# ArduiPi_V1_1.net
KiCad netlist of a schematic drawn in EAGLE
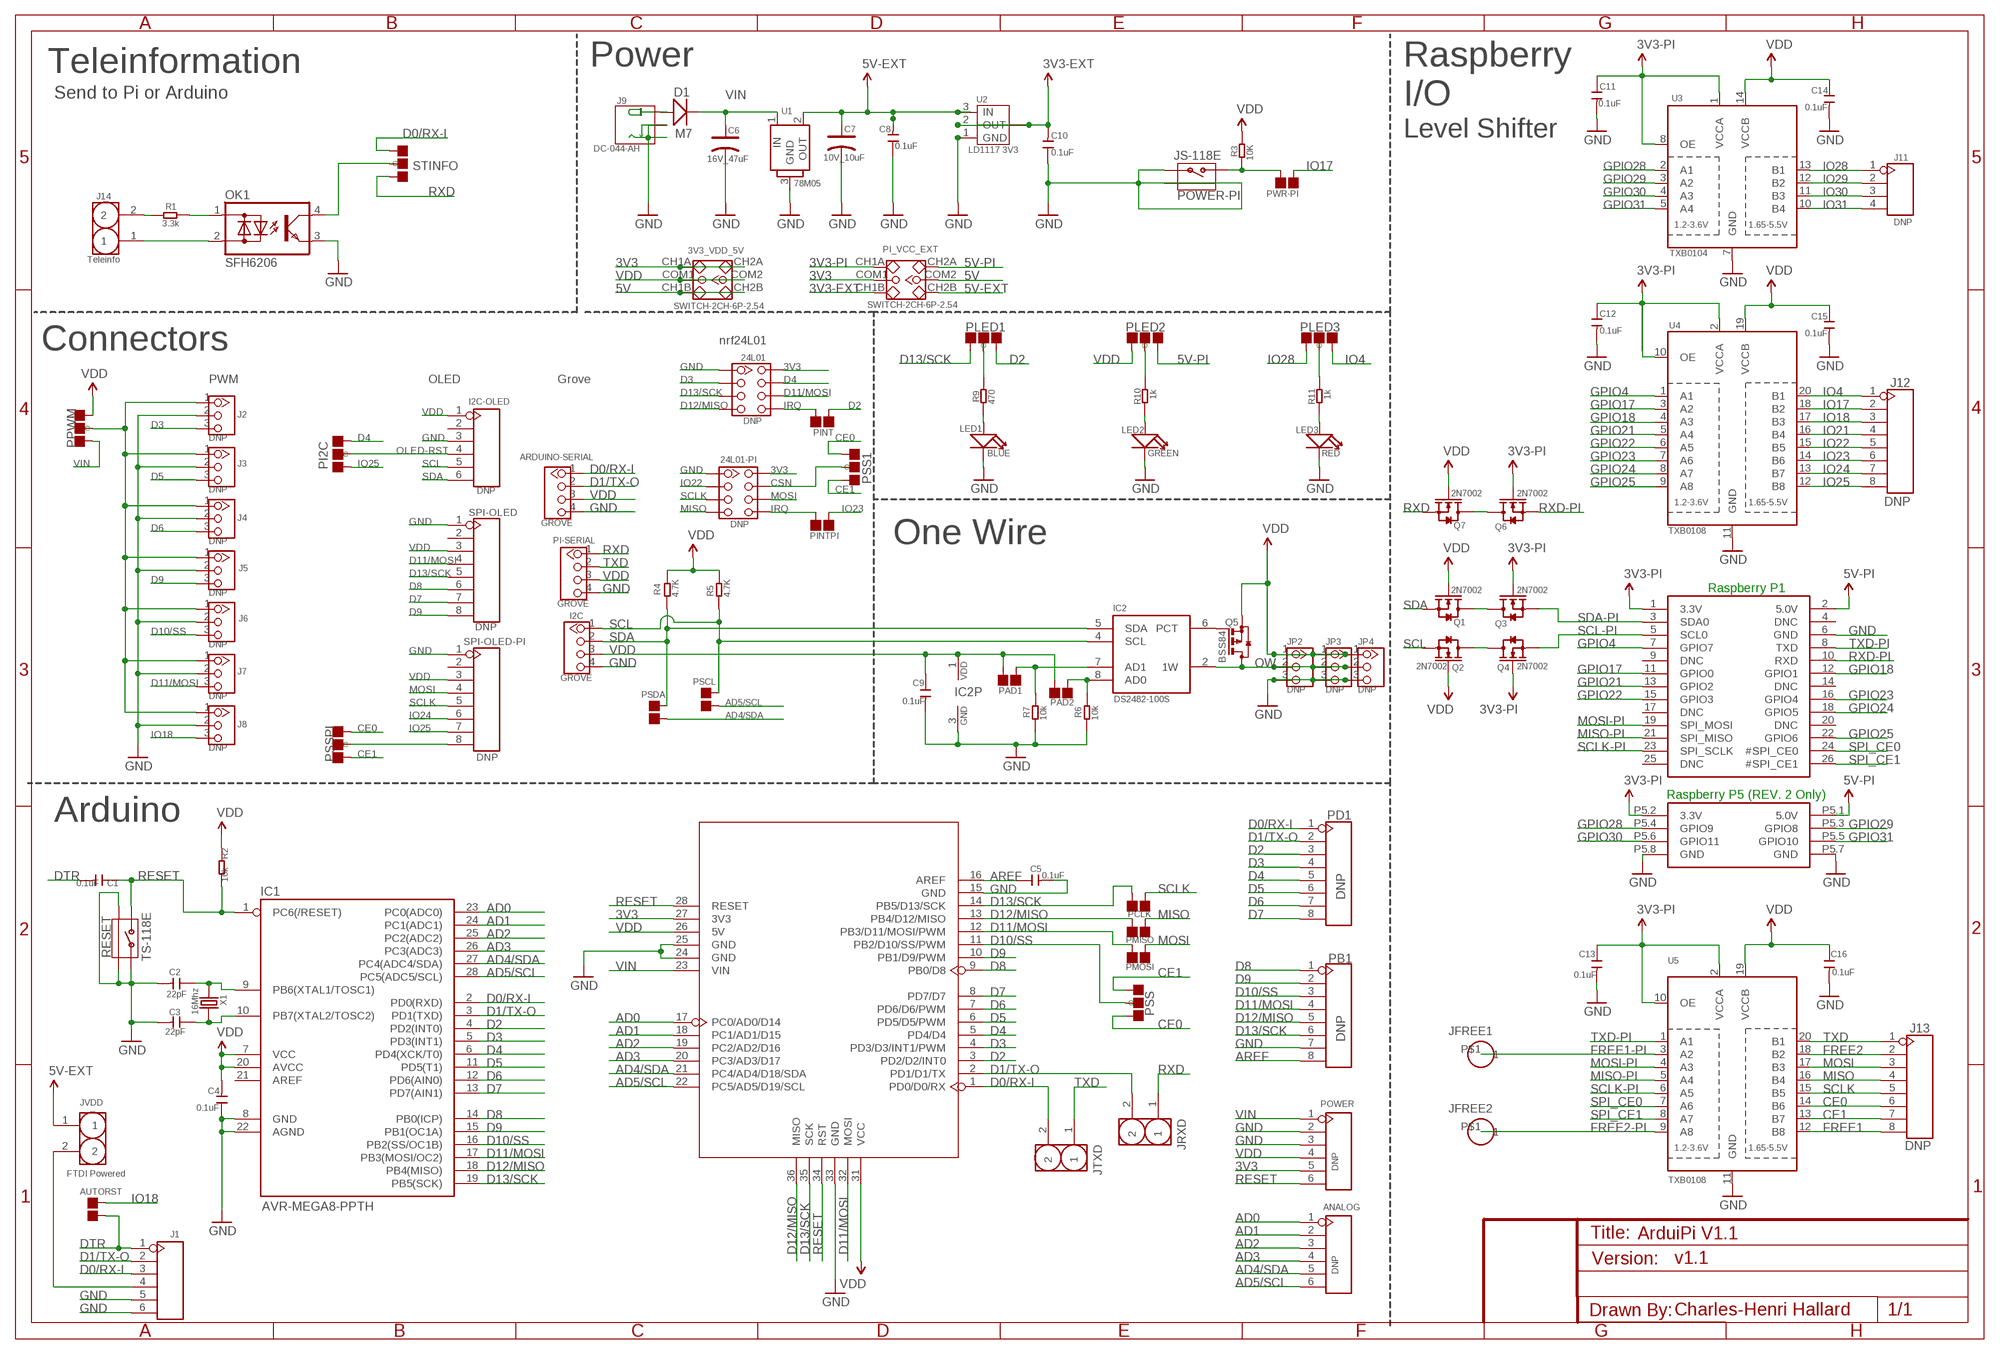
[diagram p0: schematic, sheet 1]

(export (version "E")
  (design (tool "Eeschema 10.0.6"))
  (components
    (comp (ref "3V3_VDD_5V")
      (value "SWITCH-2CH-6P-2.54")
      (footprint "eagle-import:6P-2CH-2.54-7.6X3.0")
      (libsource (lib "eagle-import") (part "SWITCH-2CH-6P"))
    )
    (comp (ref "24L01")
      (value "DNP")
      (footprint "eagle-import:2X4P-2.54")
      (libsource (lib "eagle-import") (part "HEADER-2X4P-2.54"))
    )
    (comp (ref "24L01-PI")
      (value "DNP")
      (footprint "eagle-import:2X4P-2.54")
      (libsource (lib "eagle-import") (part "HEADER-2X4P-2.54"))
    )
    (comp (ref "ANALOG")
      (value "DNP")
      (footprint "eagle-import:6P-2.54-65_35MIL")
      (libsource (lib "eagle-import") (part "HEADER-6P-65/35MIL"))
    )
    (comp (ref "ARDUINO-SERIAL")
      (value "GROVE")
      (footprint "eagle-import:4P-LEADED-2.0")
      (libsource (lib "eagle-import") (part "TWIG-2.0-LEADED"))
    )
    (comp (ref "AUTORST")
      (value "PSDA")
      (footprint "eagle-import:2P-SMD-1.78X1.27")
      (fields (field (name "PARTNO") "DNP"))
      (libsource (lib "eagle-import") (part "PAD-JUMPER-2P"))
    )
    (comp (ref "C1")
      (value "0.1uF")
      (footprint "eagle-import:C0603")
      (libsource (lib "eagle-import") (part "C-0603"))
    )
    (comp (ref "C2")
      (value "22pF")
      (footprint "eagle-import:C0603")
      (libsource (lib "eagle-import") (part "C-0603"))
    )
    (comp (ref "C3")
      (value "22pF")
      (footprint "eagle-import:C0603")
      (libsource (lib "eagle-import") (part "C-0603"))
    )
    (comp (ref "C4")
      (value "0.1uF")
      (footprint "eagle-import:C0603")
      (libsource (lib "eagle-import") (part "C-0603"))
    )
    (comp (ref "C5")
      (value "0.1uF")
      (footprint "eagle-import:C0603")
      (libsource (lib "eagle-import") (part "C-0603"))
    )
    (comp (ref "C6")
      (value "16V_47uF")
      (footprint "eagle-import:AVX-C")
      (libsource (lib "eagle-import") (part "CAP-AVX-C"))
    )
    (comp (ref "C7")
      (value "10V_10uF")
      (footprint "eagle-import:AVX-A")
      (libsource (lib "eagle-import") (part "CAP-AVX-A"))
    )
    (comp (ref "C8")
      (value "0.1uF")
      (footprint "eagle-import:C0603")
      (libsource (lib "eagle-import") (part "C-0603"))
    )
    (comp (ref "C9")
      (value "0.1uF")
      (footprint "eagle-import:C0603")
      (libsource (lib "eagle-import") (part "C-0603"))
    )
    (comp (ref "C10")
      (value "0.1uF")
      (footprint "eagle-import:C0603")
      (libsource (lib "eagle-import") (part "C-0603"))
    )
    (comp (ref "C11")
      (value "0.1uF")
      (footprint "eagle-import:C0603")
      (libsource (lib "eagle-import") (part "C-0603"))
    )
    (comp (ref "C12")
      (value "0.1uF")
      (footprint "eagle-import:C0603")
      (libsource (lib "eagle-import") (part "C-0603"))
    )
    (comp (ref "C13")
      (value "0.1uF")
      (footprint "eagle-import:C0603")
      (libsource (lib "eagle-import") (part "C-0603"))
    )
    (comp (ref "C14")
      (value "0.1uF")
      (footprint "eagle-import:C0603")
      (libsource (lib "eagle-import") (part "C-0603"))
    )
    (comp (ref "C15")
      (value "0.1uF")
      (footprint "eagle-import:C0603")
      (libsource (lib "eagle-import") (part "C-0603"))
    )
    (comp (ref "C16")
      (value "0.1uF")
      (footprint "eagle-import:C0603")
      (libsource (lib "eagle-import") (part "C-0603"))
    )
    (comp (ref "D1")
      (value "M7")
      (footprint "eagle-import:D2010")
      (libsource (lib "eagle-import") (part "D'SMA'"))
    )
    (comp (ref "I2C")
      (value "GROVE")
      (footprint "eagle-import:4P-LEADED-2.0")
      (libsource (lib "eagle-import") (part "TWIG-2.0-LEADED"))
    )
    (comp (ref "I2C-OLED")
      (value "DNP")
      (footprint "eagle-import:6P-2.54-65_35MIL")
      (libsource (lib "eagle-import") (part "HEADER-6P-65/35MIL"))
    )
    (comp (ref "IC1")
      (value "AVR-MEGA8-PPTH")
      (footprint "eagle-import:DIL28-3")
      (libsource (lib "eagle-import") (part "AVR-MEGA8-PPTH"))
    )
    (comp (ref "IC2")
      (value "DS2482-100S")
      (footprint "eagle-import:SO08")
      (libsource (lib "eagle-import") (part "DS2482-100S"))
    )
    (comp (ref "J1")
      (value "HEADER-6P-65/35MIL")
      (footprint "eagle-import:6P-2.54-65_35MIL")
      (libsource (lib "eagle-import") (part "HEADER-6P-65/35MIL"))
    )
    (comp (ref "J2")
      (value "DNP")
      (footprint "eagle-import:3P-2.54")
      (libsource (lib "eagle-import") (part "HEADER-3P-2.54"))
    )
    (comp (ref "J3")
      (value "DNP")
      (footprint "eagle-import:3P-2.54")
      (libsource (lib "eagle-import") (part "HEADER-3P-2.54"))
    )
    (comp (ref "J4")
      (value "DNP")
      (footprint "eagle-import:3P-2.54")
      (libsource (lib "eagle-import") (part "HEADER-3P-2.54"))
    )
    (comp (ref "J5")
      (value "DNP")
      (footprint "eagle-import:3P-2.54")
      (libsource (lib "eagle-import") (part "HEADER-3P-2.54"))
    )
    (comp (ref "J6")
      (value "DNP")
      (footprint "eagle-import:3P-2.54")
      (libsource (lib "eagle-import") (part "HEADER-3P-2.54"))
    )
    (comp (ref "J7")
      (value "DNP")
      (footprint "eagle-import:3P-2.54")
      (libsource (lib "eagle-import") (part "HEADER-3P-2.54"))
    )
    (comp (ref "J8")
      (value "DNP")
      (footprint "eagle-import:3P-2.54")
      (libsource (lib "eagle-import") (part "HEADER-3P-2.54"))
    )
    (comp (ref "J9")
      (value "DC-044-AH")
      (footprint "eagle-import:DC-044")
      (libsource (lib "eagle-import") (part "JACK-DC-044"))
    )
    (comp (ref "J11")
      (value "DNP")
      (footprint "eagle-import:4P-65_35MIL")
      (libsource (lib "eagle-import") (part "HEADER-4P-65/35MIL"))
    )
    (comp (ref "J12")
      (value "DNP")
      (footprint "eagle-import:8P-2.54-65_35MIL")
      (libsource (lib "eagle-import") (part "HEADER-8P-65/35MIL"))
    )
    (comp (ref "J13")
      (value "DNP")
      (footprint "eagle-import:8P-2.54-65_35MIL")
      (libsource (lib "eagle-import") (part "HEADER-8P-65/35MIL"))
    )
    (comp (ref "J14")
      (value "Teleinfo")
      (footprint "eagle-import:2P-2.54")
      (libsource (lib "eagle-import") (part "HEADER-2P-2.54"))
    )
    (comp (ref "JFREE1")
      (value "HEADER-1P-32")
      (footprint "eagle-import:1P-60_32MIL")
      (libsource (lib "eagle-import") (part "HEADER-1P-32"))
    )
    (comp (ref "JFREE2")
      (value "HEADER-1P-32")
      (footprint "eagle-import:1P-60_32MIL")
      (libsource (lib "eagle-import") (part "HEADER-1P-32"))
    )
    (comp (ref "JP2")
      (value "DNP")
      (footprint "eagle-import:3P-2.54")
      (libsource (lib "eagle-import") (part "HEADER-3P-2.54"))
    )
    (comp (ref "JP3")
      (value "DNP")
      (footprint "eagle-import:3P-2.54")
      (libsource (lib "eagle-import") (part "HEADER-3P-2.54"))
    )
    (comp (ref "JP4")
      (value "DNP")
      (footprint "eagle-import:3P-2.54")
      (libsource (lib "eagle-import") (part "HEADER-3P-2.54"))
    )
    (comp (ref "JRXD")
      (value "J2")
      (footprint "eagle-import:2P-2.54")
      (libsource (lib "eagle-import") (part "HEADER-2P-2.54"))
    )
    (comp (ref "JTXD")
      (value "J1")
      (footprint "eagle-import:2P-2.54")
      (libsource (lib "eagle-import") (part "HEADER-2P-2.54"))
    )
    (comp (ref "JVDD")
      (value "FTDI Powered")
      (footprint "eagle-import:2P-2.54")
      (libsource (lib "eagle-import") (part "HEADER-2P-2.54"))
    )
    (comp (ref "LED1")
      (value "BLUE")
      (footprint "eagle-import:LED-0603")
      (libsource (lib "eagle-import") (part "LED'0603'"))
    )
    (comp (ref "LED2")
      (value "GREEN")
      (footprint "eagle-import:LED-0603")
      (libsource (lib "eagle-import") (part "LED'0603'"))
    )
    (comp (ref "LED3")
      (value "RED")
      (footprint "eagle-import:LED-0603")
      (libsource (lib "eagle-import") (part "LED'0603'"))
    )
    (comp (ref "OK1")
      (value "SFH6206")
      (footprint "eagle-import:DIL4-SMD")
      (fields (field (name "MF") "VISHAY/TELEFUNKEN") (field (name "MPN") "SFH6206-3"))
      (libsource (lib "eagle-import") (part "SFH6206"))
    )
    (comp (ref "PAD1")
      (value "PAD1")
      (footprint "eagle-import:2P-SMD-1.78X1.27")
      (fields (field (name "PARTNO") "DNP") (field (name "PARTNO_1") "DNP"))
      (libsource (lib "eagle-import") (part "PAD-JUMPER-2P"))
    )
    (comp (ref "PAD2")
      (value "PAD2")
      (footprint "eagle-import:2P-SMD-1.78X1.27")
      (fields (field (name "PARTNO") "DNP") (field (name "PARTNO_1") "DNP"))
      (libsource (lib "eagle-import") (part "PAD-JUMPER-2P"))
    )
    (comp (ref "PB1")
      (value "DNP")
      (footprint "eagle-import:8P-2.54-65_35MIL")
      (libsource (lib "eagle-import") (part "HEADER-8P-65/35MIL"))
    )
    (comp (ref "PCLK")
      (value "PCLK")
      (footprint "eagle-import:2P-SMD-1.78X1.27")
      (fields (field (name "PARTNO") "DNP"))
      (libsource (lib "eagle-import") (part "PAD-JUMPER-2P"))
    )
    (comp (ref "PD1")
      (value "DNP")
      (footprint "eagle-import:8P-2.54-65_35MIL")
      (libsource (lib "eagle-import") (part "HEADER-8P-65/35MIL"))
    )
    (comp (ref "PI-P1")
      (value "PI-P1")
      (footprint "eagle-import:RASPBERRYPI_SHIELD")
      (libsource (lib "eagle-import") (part "RASPBERRYPI_BV2"))
    )
    (comp (ref "PI-SERIAL")
      (value "GROVE")
      (footprint "eagle-import:4P-LEADED-2.0")
      (libsource (lib "eagle-import") (part "TWIG-2.0-LEADED"))
    )
    (comp (ref "PI2C")
      (value "PAD-JUMPER-3P-40*40")
      (footprint "eagle-import:3P-SMD-4.1X1.5")
      (fields (field (name "PARTNO") "DNP") (field (name "PARTNO_1") "DNP"))
      (libsource (lib "eagle-import") (part "PAD-JUMPER-3P-4040"))
    )
    (comp (ref "PINT")
      (value "PINT")
      (footprint "eagle-import:2P-SMD-1.78X1.27")
      (fields (field (name "PARTNO") "DNP"))
      (libsource (lib "eagle-import") (part "PAD-JUMPER-2P"))
    )
    (comp (ref "PINTPI")
      (value "PINTPI")
      (footprint "eagle-import:2P-SMD-1.78X1.27")
      (fields (field (name "PARTNO") "DNP"))
      (libsource (lib "eagle-import") (part "PAD-JUMPER-2P"))
    )
    (comp (ref "PI_VCC_EXT")
      (value "SWITCH-2CH-6P-2.54")
      (footprint "eagle-import:6P-2CH-2.54-7.6X3.0")
      (libsource (lib "eagle-import") (part "SWITCH-2CH-6P"))
    )
    (comp (ref "PLED1")
      (value "PAD-JUMPER-3P-40*40")
      (footprint "eagle-import:3P-SMD-4.1X1.5")
      (fields (field (name "PARTNO") "DNP") (field (name "PARTNO_1") "DNP"))
      (libsource (lib "eagle-import") (part "PAD-JUMPER-3P-4040"))
    )
    (comp (ref "PLED2")
      (value "PAD-JUMPER-3P-40*40")
      (footprint "eagle-import:3P-SMD-4.1X1.5")
      (fields (field (name "PARTNO") "DNP"))
      (libsource (lib "eagle-import") (part "PAD-JUMPER-3P-4040"))
    )
    (comp (ref "PLED3")
      (value "PAD-JUMPER-3P-40*40")
      (footprint "eagle-import:3P-SMD-4.1X1.5")
      (fields (field (name "PARTNO") "DNP") (field (name "PARTNO_1") "DNP"))
      (libsource (lib "eagle-import") (part "PAD-JUMPER-3P-4040"))
    )
    (comp (ref "PMISO")
      (value "PMISO")
      (footprint "eagle-import:2P-SMD-1.78X1.27")
      (fields (field (name "PARTNO") "DNP"))
      (libsource (lib "eagle-import") (part "PAD-JUMPER-2P"))
    )
    (comp (ref "PMOSI")
      (value "PMOSI")
      (footprint "eagle-import:2P-SMD-1.78X1.27")
      (fields (field (name "PARTNO") "DNP"))
      (libsource (lib "eagle-import") (part "PAD-JUMPER-2P"))
    )
    (comp (ref "POWER")
      (value "DNP")
      (footprint "eagle-import:6P-2.54-65_35MIL")
      (libsource (lib "eagle-import") (part "HEADER-6P-65/35MIL"))
    )
    (comp (ref "POWER-PI")
      (value "JS-118E")
      (footprint "eagle-import:4P-SMD-7X3.5X3.5H")
      (libsource (lib "eagle-import") (part "BUTTON-4P-REINFORCE'TS-118E'"))
    )
    (comp (ref "PPWM")
      (value "PAD-JUMPER-3P-40*40")
      (footprint "eagle-import:3P-SMD-4.1X1.5")
      (fields (field (name "PARTNO") "DNP") (field (name "PARTNO_1") "DNP"))
      (libsource (lib "eagle-import") (part "PAD-JUMPER-3P-4040"))
    )
    (comp (ref "PSCL")
      (value "PSCL")
      (footprint "eagle-import:2P-SMD-1.78X1.27")
      (fields (field (name "PARTNO") "DNP"))
      (libsource (lib "eagle-import") (part "PAD-JUMPER-2P"))
    )
    (comp (ref "PSDA")
      (value "PSDA")
      (footprint "eagle-import:2P-SMD-1.78X1.27")
      (fields (field (name "PARTNO") "DNP"))
      (libsource (lib "eagle-import") (part "PAD-JUMPER-2P"))
    )
    (comp (ref "PSS")
      (value "PAD-JUMPER-3P-40*40")
      (footprint "eagle-import:3P-SMD-4.1X1.5")
      (fields (field (name "PARTNO") "DNP"))
      (libsource (lib "eagle-import") (part "PAD-JUMPER-3P-4040"))
    )
    (comp (ref "PSS1")
      (value "PAD-JUMPER-3P-40*40")
      (footprint "eagle-import:3P-SMD-4.1X1.5")
      (fields (field (name "PARTNO") "DNP") (field (name "PARTNO_1") "DNP"))
      (libsource (lib "eagle-import") (part "PAD-JUMPER-3P-4040"))
    )
    (comp (ref "PSSPI")
      (value "PAD-JUMPER-3P-40*40")
      (footprint "eagle-import:3P-SMD-4.1X1.5")
      (fields (field (name "PARTNO") "DNP") (field (name "PARTNO_1") "DNP"))
      (libsource (lib "eagle-import") (part "PAD-JUMPER-3P-4040"))
    )
    (comp (ref "PWR-PI")
      (value "PINT")
      (footprint "eagle-import:2P-SMD-1.78X1.27")
      (fields (field (name "PARTNO") "DNP"))
      (libsource (lib "eagle-import") (part "PAD-JUMPER-2P"))
    )
    (comp (ref "Q1")
      (value "2N7002")
      (footprint "eagle-import:SOT23")
      (libsource (lib "eagle-import") (part "MOSFET-N-SOT23"))
    )
    (comp (ref "Q2")
      (value "2N7002")
      (footprint "eagle-import:SOT23")
      (libsource (lib "eagle-import") (part "MOSFET-N-SOT23"))
    )
    (comp (ref "Q3")
      (value "2N7002")
      (footprint "eagle-import:SOT23")
      (libsource (lib "eagle-import") (part "MOSFET-N-SOT23"))
    )
    (comp (ref "Q4")
      (value "2N7002")
      (footprint "eagle-import:SOT23")
      (libsource (lib "eagle-import") (part "MOSFET-N-SOT23"))
    )
    (comp (ref "Q5")
      (value "BSS84")
      (footprint "eagle-import:SOT23")
      (libsource (lib "eagle-import") (part "BSS84"))
    )
    (comp (ref "Q6")
      (value "2N7002")
      (footprint "eagle-import:SOT23")
      (libsource (lib "eagle-import") (part "MOSFET-N-SOT23"))
    )
    (comp (ref "Q7")
      (value "2N7002")
      (footprint "eagle-import:SOT23")
      (libsource (lib "eagle-import") (part "MOSFET-N-SOT23"))
    )
    (comp (ref "R1")
      (value "3.3k")
      (footprint "eagle-import:R0603")
      (libsource (lib "eagle-import") (part "R-0603"))
    )
    (comp (ref "R2")
      (value "10k")
      (footprint "eagle-import:R0603")
      (libsource (lib "eagle-import") (part "R-0603"))
    )
    (comp (ref "R3")
      (value "10K")
      (footprint "eagle-import:R0603")
      (libsource (lib "eagle-import") (part "R-0603"))
    )
    (comp (ref "R4")
      (value "4.7K")
      (footprint "eagle-import:R0603")
      (libsource (lib "eagle-import") (part "R-0603"))
    )
    (comp (ref "R5")
      (value "4.7K")
      (footprint "eagle-import:R0603")
      (libsource (lib "eagle-import") (part "R-0603"))
    )
    (comp (ref "R6")
      (value "10k")
      (footprint "eagle-import:R0603")
      (libsource (lib "eagle-import") (part "R-0603"))
    )
    (comp (ref "R7")
      (value "10k")
      (footprint "eagle-import:R0603")
      (libsource (lib "eagle-import") (part "R-0603"))
    )
    (comp (ref "R9")
      (value "470")
      (footprint "eagle-import:R0603")
      (libsource (lib "eagle-import") (part "R-0603"))
    )
    (comp (ref "R10")
      (value "1k")
      (footprint "eagle-import:R0603")
      (libsource (lib "eagle-import") (part "R-0603"))
    )
    (comp (ref "R11")
      (value "1k")
      (footprint "eagle-import:R0603")
      (libsource (lib "eagle-import") (part "R-0603"))
    )
    (comp (ref "RESET")
      (value "TS-118E")
      (footprint "eagle-import:4P-SMD-7X3.5X3.5H")
      (libsource (lib "eagle-import") (part "BUTTON-4P-REINFORCE'TS-118E'"))
    )
    (comp (ref "SPI-OLED")
      (value "DNP")
      (footprint "eagle-import:8P-2.54-65_35MIL")
      (libsource (lib "eagle-import") (part "HEADER-8P-65/35MIL"))
    )
    (comp (ref "SPI-OLED-PI")
      (value "DNP")
      (footprint "eagle-import:8P-2.54-65_35MIL")
      (libsource (lib "eagle-import") (part "HEADER-8P-65/35MIL"))
    )
    (comp (ref "STINFO")
      (value "PAD-JUMPER-3P-40*40")
      (footprint "eagle-import:3P-SMD-4.1X1.5")
      (fields (field (name "PARTNO") "DNP"))
      (libsource (lib "eagle-import") (part "PAD-JUMPER-3P-4040"))
    )
    (comp (ref "U1")
      (value "78M05")
      (footprint "eagle-import:TO252")
      (libsource (lib "eagle-import") (part "78M05-TO252"))
    )
    (comp (ref "U2")
      (value "LD1117 3V3")
      (footprint "eagle-import:SOT-223")
      (libsource (lib "eagle-import") (part "LD1117SOT223"))
    )
    (comp (ref "U3")
      (value "TXB0104")
      (footprint "eagle-import:TSSOP14")
      (libsource (lib "eagle-import") (part "TXB0104PWR"))
    )
    (comp (ref "U4")
      (value "TXB0108")
      (footprint "eagle-import:TSSOP20")
      (libsource (lib "eagle-import") (part "TXB0108PWR"))
    )
    (comp (ref "U5")
      (value "TXB0108")
      (footprint "eagle-import:TSSOP20")
      (libsource (lib "eagle-import") (part "TXB0108PWR"))
    )
    (comp (ref "U6")
      (value "ARDUINO'W/-SILK")
      (footprint "eagle-import:ARDUINO")
      (libsource (lib "eagle-import") (part "ARDUINO'W/-SILK"))
    )
    (comp (ref "X1")
      (value "16Mhz")
      (footprint "eagle-import:2P-SMD-5X3.2")
      (libsource (lib "eagle-import") (part "CRYSTAL'5032'"))
    )
  )
  (nets
    (net (code "1") (name "/3V3") (class "Default")
      (node (ref "24L01") (pin "8") (pinfunction "8_8") (pintype "bidirectional"))
      (node (ref "24L01-PI") (pin "8") (pinfunction "8_8") (pintype "bidirectional"))
      (node (ref "3V3_VDD_5V") (pin "CH1A") (pinfunction "CH1A_CH1A") (pintype "bidirectional"))
      (node (ref "3V3_VDD_5V") (pin "CH2A") (pinfunction "CH2A_CH2A") (pintype "bidirectional"))
      (node (ref "PI_VCC_EXT") (pin "COM1") (pinfunction "COM1_COM1") (pintype "bidirectional"))
      (node (ref "POWER") (pin "5") (pinfunction "5_5") (pintype "bidirectional"))
      (node (ref "U6") (pin "27") (pinfunction "3V3_27") (pintype "bidirectional"))
    )
    (net (code "2") (name "/5V") (class "Default")
      (node (ref "3V3_VDD_5V") (pin "CH1B") (pinfunction "CH1B_CH1B") (pintype "bidirectional"))
      (node (ref "3V3_VDD_5V") (pin "CH2B") (pinfunction "CH2B_CH2B") (pintype "bidirectional"))
      (node (ref "PI_VCC_EXT") (pin "COM2") (pinfunction "COM2_COM2") (pintype "bidirectional"))
    )
    (net (code "3") (name "/AD0") (class "Default")
      (node (ref "ANALOG") (pin "1") (pinfunction "1_1") (pintype "bidirectional"))
      (node (ref "IC1") (pin "23") (pinfunction "PC0(ADC0)_23") (pintype "bidirectional"))
      (node (ref "U6") (pin "17") (pinfunction "PC0/AD0/D14_17") (pintype "bidirectional"))
    )
    (net (code "4") (name "/AD1") (class "Default")
      (node (ref "ANALOG") (pin "2") (pinfunction "2_2") (pintype "bidirectional"))
      (node (ref "IC1") (pin "24") (pinfunction "PC1(ADC1)_24") (pintype "bidirectional"))
      (node (ref "U6") (pin "18") (pinfunction "PC1/AD1/D15_18") (pintype "bidirectional"))
    )
    (net (code "5") (name "/AD2") (class "Default")
      (node (ref "ANALOG") (pin "3") (pinfunction "3_3") (pintype "bidirectional"))
      (node (ref "IC1") (pin "25") (pinfunction "PC2(ADC2)_25") (pintype "bidirectional"))
      (node (ref "U6") (pin "19") (pinfunction "PC2/AD2/D16_19") (pintype "bidirectional"))
    )
    (net (code "6") (name "/AD3") (class "Default")
      (node (ref "ANALOG") (pin "4") (pinfunction "4_4") (pintype "bidirectional"))
      (node (ref "IC1") (pin "26") (pinfunction "PC3(ADC3)_26") (pintype "bidirectional"))
      (node (ref "U6") (pin "20") (pinfunction "PC3/AD3/D17_20") (pintype "bidirectional"))
    )
    (net (code "7") (name "/AD4{slash}SDA") (class "Default")
      (node (ref "ANALOG") (pin "5") (pinfunction "5_5") (pintype "bidirectional"))
      (node (ref "IC1") (pin "27") (pinfunction "PC4(ADC4/SDA)_27") (pintype "bidirectional"))
      (node (ref "PSDA") (pin "1") (pinfunction "1_1") (pintype "bidirectional"))
      (node (ref "U6") (pin "21") (pinfunction "PC4/AD4/D18/SDA_21") (pintype "bidirectional"))
    )
    (net (code "8") (name "/AD5{slash}SCL") (class "Default")
      (node (ref "ANALOG") (pin "6") (pinfunction "6_6") (pintype "bidirectional"))
      (node (ref "IC1") (pin "28") (pinfunction "PC5(ADC5/SCL)_28") (pintype "bidirectional"))
      (node (ref "PSCL") (pin "1") (pinfunction "1_1") (pintype "bidirectional"))
      (node (ref "U6") (pin "22") (pinfunction "PC5/AD5/D19/SCL_22") (pintype "bidirectional"))
    )
    (net (code "9") (name "/AREF") (class "Default")
      (node (ref "C5") (pin "1") (pinfunction "1_1") (pintype "passive"))
      (node (ref "PB1") (pin "8") (pinfunction "8_8") (pintype "bidirectional"))
      (node (ref "U6") (pin "16") (pinfunction "AREF_16") (pintype "bidirectional"))
    )
    (net (code "10") (name "/CE0") (class "Default")
      (node (ref "J13") (pin "6") (pinfunction "6_6") (pintype "bidirectional"))
      (node (ref "PSS") (pin "11") (pinfunction "R_11") (pintype "bidirectional"))
      (node (ref "PSS1") (pin "00") (pinfunction "L_00") (pintype "bidirectional"))
      (node (ref "PSSPI") (pin "11") (pinfunction "R_11") (pintype "bidirectional"))
      (node (ref "U5") (pin "14") (pinfunction "B6_14") (pintype "bidirectional"))
    )
    (net (code "11") (name "/CE1") (class "Default")
      (node (ref "J13") (pin "7") (pinfunction "7_7") (pintype "bidirectional"))
      (node (ref "PSS") (pin "00") (pinfunction "L_00") (pintype "bidirectional"))
      (node (ref "PSS1") (pin "11") (pinfunction "R_11") (pintype "bidirectional"))
      (node (ref "PSSPI") (pin "00") (pinfunction "L_00") (pintype "bidirectional"))
      (node (ref "U5") (pin "13") (pinfunction "B7_13") (pintype "bidirectional"))
    )
    (net (code "12") (name "/CSN") (class "Default")
      (node (ref "24L01-PI") (pin "7") (pinfunction "7_7") (pintype "bidirectional"))
      (node (ref "PSS1") (pin "MM") (pinfunction "C_MM") (pintype "bidirectional"))
    )
    (net (code "13") (name "/D0{slash}RX-I") (class "Default")
      (node (ref "ARDUINO-SERIAL") (pin "1") (pinfunction "1_1") (pintype "bidirectional"))
      (node (ref "IC1") (pin "2") (pinfunction "PD0(RXD)_2") (pintype "bidirectional"))
      (node (ref "J1") (pin "3") (pinfunction "3_3") (pintype "bidirectional"))
      (node (ref "JTXD") (pin "2") (pinfunction "2_2") (pintype "bidirectional"))
      (node (ref "PD1") (pin "1") (pinfunction "1_1") (pintype "bidirectional"))
      (node (ref "STINFO") (pin "00") (pinfunction "L_00") (pintype "bidirectional"))
      (node (ref "U6") (pin "1") (pinfunction "PD0/D0/RX_1") (pintype "bidirectional"))
    )
    (net (code "14") (name "/D1{slash}TX-O") (class "Default")
      (node (ref "ARDUINO-SERIAL") (pin "2") (pinfunction "2_2") (pintype "bidirectional"))
      (node (ref "IC1") (pin "3") (pinfunction "PD1(TXD)_3") (pintype "bidirectional"))
      (node (ref "J1") (pin "2") (pinfunction "2_2") (pintype "bidirectional"))
      (node (ref "JRXD") (pin "2") (pinfunction "2_2") (pintype "bidirectional"))
      (node (ref "PD1") (pin "2") (pinfunction "2_2") (pintype "bidirectional"))
      (node (ref "U6") (pin "2") (pinfunction "PD1/D1/TX_2") (pintype "bidirectional"))
    )
    (net (code "15") (name "/D2") (class "Default")
      (node (ref "IC1") (pin "4") (pinfunction "PD2(INT0)_4") (pintype "bidirectional"))
      (node (ref "PD1") (pin "3") (pinfunction "3_3") (pintype "bidirectional"))
      (node (ref "PINT") (pin "1") (pinfunction "1_1") (pintype "bidirectional"))
      (node (ref "PLED1") (pin "11") (pinfunction "R_11") (pintype "bidirectional"))
      (node (ref "U6") (pin "3") (pinfunction "PD2/D2/INT0_3") (pintype "bidirectional"))
    )
    (net (code "16") (name "/D3") (class "Default")
      (node (ref "24L01") (pin "2") (pinfunction "2_2") (pintype "bidirectional"))
      (node (ref "IC1") (pin "5") (pinfunction "PD3(INT1)_5") (pintype "bidirectional"))
      (node (ref "J2") (pin "3") (pinfunction "P$3_3") (pintype "bidirectional"))
      (node (ref "PD1") (pin "4") (pinfunction "4_4") (pintype "bidirectional"))
      (node (ref "U6") (pin "4") (pinfunction "PD3/D3/INT1/PWM_4") (pintype "bidirectional"))
    )
    (net (code "17") (name "/D4") (class "Default")
      (node (ref "24L01") (pin "7") (pinfunction "7_7") (pintype "bidirectional"))
      (node (ref "IC1") (pin "6") (pinfunction "PD4(XCK/T0)_6") (pintype "bidirectional"))
      (node (ref "PD1") (pin "5") (pinfunction "5_5") (pintype "bidirectional"))
      (node (ref "PI2C") (pin "11") (pinfunction "R_11") (pintype "bidirectional"))
      (node (ref "U6") (pin "5") (pinfunction "PD4/D4_5") (pintype "bidirectional"))
    )
    (net (code "18") (name "/D5") (class "Default")
      (node (ref "IC1") (pin "11") (pinfunction "PD5(T1)_11") (pintype "bidirectional"))
      (node (ref "J3") (pin "3") (pinfunction "P$3_3") (pintype "bidirectional"))
      (node (ref "PD1") (pin "6") (pinfunction "6_6") (pintype "bidirectional"))
      (node (ref "U6") (pin "6") (pinfunction "PD5/D5/PWM_6") (pintype "bidirectional"))
    )
    (net (code "19") (name "/D6") (class "Default")
      (node (ref "IC1") (pin "12") (pinfunction "PD6(AIN0)_12") (pintype "bidirectional"))
      (node (ref "J4") (pin "3") (pinfunction "P$3_3") (pintype "bidirectional"))
      (node (ref "PD1") (pin "7") (pinfunction "7_7") (pintype "bidirectional"))
      (node (ref "U6") (pin "7") (pinfunction "PD6/D6/PWM_7") (pintype "bidirectional"))
    )
    (net (code "20") (name "/D7") (class "Default")
      (node (ref "IC1") (pin "13") (pinfunction "PD7(AIN1)_13") (pintype "bidirectional"))
      (node (ref "PD1") (pin "8") (pinfunction "8_8") (pintype "bidirectional"))
      (node (ref "SPI-OLED") (pin "7") (pinfunction "7_7") (pintype "bidirectional"))
      (node (ref "U6") (pin "8") (pinfunction "PD7/D7_8") (pintype "bidirectional"))
    )
    (net (code "21") (name "/D8") (class "Default")
      (node (ref "IC1") (pin "14") (pinfunction "PB0(ICP)_14") (pintype "bidirectional"))
      (node (ref "PB1") (pin "1") (pinfunction "1_1") (pintype "bidirectional"))
      (node (ref "SPI-OLED") (pin "6") (pinfunction "6_6") (pintype "bidirectional"))
      (node (ref "U6") (pin "9") (pinfunction "PB0/D8_9") (pintype "bidirectional"))
    )
    (net (code "22") (name "/D9") (class "Default")
      (node (ref "IC1") (pin "15") (pinfunction "PB1(OC1A)_15") (pintype "bidirectional"))
      (node (ref "J5") (pin "3") (pinfunction "P$3_3") (pintype "bidirectional"))
      (node (ref "PB1") (pin "2") (pinfunction "2_2") (pintype "bidirectional"))
      (node (ref "SPI-OLED") (pin "8") (pinfunction "8_8") (pintype "bidirectional"))
      (node (ref "U6") (pin "10") (pinfunction "PB1/D9/PWM_10") (pintype "bidirectional"))
    )
    (net (code "23") (name "/D10{slash}SS") (class "Default")
      (node (ref "IC1") (pin "16") (pinfunction "PB2(SS/OC1B)_16") (pintype "bidirectional"))
      (node (ref "J6") (pin "3") (pinfunction "P$3_3") (pintype "bidirectional"))
      (node (ref "PB1") (pin "3") (pinfunction "3_3") (pintype "bidirectional"))
      (node (ref "PSS") (pin "MM") (pinfunction "C_MM") (pintype "bidirectional"))
      (node (ref "U6") (pin "11") (pinfunction "PB2/D10/SS/PWM_11") (pintype "bidirectional"))
    )
    (net (code "24") (name "/D11{slash}MOSI") (class "Default")
      (node (ref "24L01") (pin "6") (pinfunction "6_6") (pintype "bidirectional"))
      (node (ref "IC1") (pin "17") (pinfunction "PB3(MOSI/OC2)_17") (pintype "bidirectional"))
      (node (ref "J7") (pin "3") (pinfunction "P$3_3") (pintype "bidirectional"))
      (node (ref "PB1") (pin "4") (pinfunction "4_4") (pintype "bidirectional"))
      (node (ref "PMOSI") (pin "2") (pinfunction "2_2") (pintype "bidirectional"))
      (node (ref "SPI-OLED") (pin "4") (pinfunction "4_4") (pintype "bidirectional"))
      (node (ref "U6") (pin "12") (pinfunction "PB3/D11/MOSI/PWM_12") (pintype "bidirectional"))
      (node (ref "U6") (pin "32") (pinfunction "MOSI_32") (pintype "bidirectional"))
    )
    (net (code "25") (name "/D12{slash}MISO") (class "Default")
      (node (ref "24L01") (pin "4") (pinfunction "4_4") (pintype "bidirectional"))
      (node (ref "IC1") (pin "18") (pinfunction "PB4(MISO)_18") (pintype "bidirectional"))
      (node (ref "PB1") (pin "5") (pinfunction "5_5") (pintype "bidirectional"))
      (node (ref "PMISO") (pin "2") (pinfunction "2_2") (pintype "bidirectional"))
      (node (ref "U6") (pin "13") (pinfunction "PB4/D12/MISO_13") (pintype "bidirectional"))
      (node (ref "U6") (pin "36") (pinfunction "MISO_36") (pintype "bidirectional"))
    )
    (net (code "26") (name "/D13{slash}SCK") (class "Default")
      (node (ref "24L01") (pin "3") (pinfunction "3_3") (pintype "bidirectional"))
      (node (ref "IC1") (pin "19") (pinfunction "PB5(SCK)_19") (pintype "bidirectional"))
      (node (ref "PB1") (pin "6") (pinfunction "6_6") (pintype "bidirectional"))
      (node (ref "PCLK") (pin "2") (pinfunction "2_2") (pintype "bidirectional"))
      (node (ref "PLED1") (pin "00") (pinfunction "L_00") (pintype "bidirectional"))
      (node (ref "SPI-OLED") (pin "5") (pinfunction "5_5") (pintype "bidirectional"))
      (node (ref "U6") (pin "14") (pinfunction "PB5/D13/SCK_14") (pintype "bidirectional"))
      (node (ref "U6") (pin "35") (pinfunction "SCK_35") (pintype "bidirectional"))
    )
    (net (code "27") (name "/DTR") (class "Default")
      (node (ref "AUTORST") (pin "1") (pinfunction "1_1") (pintype "bidirectional"))
      (node (ref "C1") (pin "2") (pinfunction "2_2") (pintype "passive"))
      (node (ref "J1") (pin "1") (pinfunction "1_1") (pintype "bidirectional"))
    )
    (net (code "28") (name "/FREE1") (class "Default")
      (node (ref "J13") (pin "8") (pinfunction "8_8") (pintype "bidirectional"))
      (node (ref "U5") (pin "12") (pinfunction "B8_12") (pintype "bidirectional"))
    )
    (net (code "29") (name "/FREE1-PI") (class "Default")
      (node (ref "JFREE1") (pin "P$1") (pinfunction "1_P$1") (pintype "bidirectional"))
      (node (ref "U5") (pin "3") (pinfunction "A2_3") (pintype "bidirectional"))
    )
    (net (code "30") (name "/FREE2") (class "Default")
      (node (ref "J13") (pin "2") (pinfunction "2_2") (pintype "bidirectional"))
      (node (ref "U5") (pin "18") (pinfunction "B2_18") (pintype "bidirectional"))
    )
    (net (code "31") (name "/FREE2-PI") (class "Default")
      (node (ref "JFREE2") (pin "P$1") (pinfunction "1_P$1") (pintype "bidirectional"))
      (node (ref "U5") (pin "9") (pinfunction "A8_9") (pintype "bidirectional"))
    )
    (net (code "32") (name "/GPIO4") (class "Default")
      (node (ref "PI-P1") (pin "7") (pinfunction "GPIO7_7") (pintype "bidirectional"))
      (node (ref "U4") (pin "1") (pinfunction "A1_1") (pintype "bidirectional"))
    )
    (net (code "33") (name "/GPIO17") (class "Default")
      (node (ref "PI-P1") (pin "11") (pinfunction "GPIO0_11") (pintype "bidirectional"))
      (node (ref "U4") (pin "3") (pinfunction "A2_3") (pintype "bidirectional"))
    )
    (net (code "34") (name "/GPIO18") (class "Default")
      (node (ref "PI-P1") (pin "12") (pinfunction "GPIO1_12") (pintype "bidirectional"))
      (node (ref "U4") (pin "4") (pinfunction "A3_4") (pintype "bidirectional"))
    )
    (net (code "35") (name "/GPIO21") (class "Default")
      (node (ref "PI-P1") (pin "13") (pinfunction "GPIO2_13") (pintype "bidirectional"))
      (node (ref "U4") (pin "5") (pinfunction "A4_5") (pintype "bidirectional"))
    )
    (net (code "36") (name "/GPIO22") (class "Default")
      (node (ref "PI-P1") (pin "15") (pinfunction "GPIO3_15") (pintype "bidirectional"))
      (node (ref "U4") (pin "6") (pinfunction "A5_6") (pintype "bidirectional"))
    )
    (net (code "37") (name "/GPIO23") (class "Default")
      (node (ref "PI-P1") (pin "16") (pinfunction "GPIO4_16") (pintype "bidirectional"))
      (node (ref "U4") (pin "7") (pinfunction "A6_7") (pintype "bidirectional"))
    )
    (net (code "38") (name "/GPIO24") (class "Default")
      (node (ref "PI-P1") (pin "18") (pinfunction "GPIO5_18") (pintype "bidirectional"))
      (node (ref "U4") (pin "8") (pinfunction "A7_8") (pintype "bidirectional"))
    )
    (net (code "39") (name "/GPIO25") (class "Default")
      (node (ref "PI-P1") (pin "22") (pinfunction "GPIO6_22") (pintype "bidirectional"))
      (node (ref "U4") (pin "9") (pinfunction "A8_9") (pintype "bidirectional"))
    )
    (net (code "40") (name "/GPIO28") (class "Default")
      (node (ref "PI-P1") (pin "P5.4") (pinfunction "GPIO9_P5.4") (pintype "bidirectional"))
      (node (ref "U3") (pin "2") (pinfunction "A1_2") (pintype "bidirectional"))
    )
    (net (code "41") (name "/GPIO29") (class "Default")
      (node (ref "PI-P1") (pin "P5.3") (pinfunction "GPIO8_P5.3") (pintype "bidirectional"))
      (node (ref "U3") (pin "3") (pinfunction "A2_3") (pintype "bidirectional"))
    )
    (net (code "42") (name "/GPIO30") (class "Default")
      (node (ref "PI-P1") (pin "P5.6") (pinfunction "GPIO11_P5.6") (pintype "bidirectional"))
      (node (ref "U3") (pin "4") (pinfunction "A3_4") (pintype "bidirectional"))
    )
    (net (code "43") (name "/GPIO31") (class "Default")
      (node (ref "PI-P1") (pin "P5.5") (pinfunction "GPIO10_P5.5") (pintype "bidirectional"))
      (node (ref "U3") (pin "5") (pinfunction "A4_5") (pintype "bidirectional"))
    )
    (net (code "44") (name "/IO4") (class "Default")
      (node (ref "J12") (pin "1") (pinfunction "1_1") (pintype "bidirectional"))
      (node (ref "PLED3") (pin "11") (pinfunction "R_11") (pintype "bidirectional"))
      (node (ref "U4") (pin "20") (pinfunction "B1_20") (pintype "bidirectional"))
    )
    (net (code "45") (name "/IO17") (class "Default")
      (node (ref "J12") (pin "2") (pinfunction "2_2") (pintype "bidirectional"))
      (node (ref "PWR-PI") (pin "1") (pinfunction "1_1") (pintype "bidirectional"))
      (node (ref "U4") (pin "18") (pinfunction "B2_18") (pintype "bidirectional"))
    )
    (net (code "46") (name "/IO18") (class "Default")
      (node (ref "AUTORST") (pin "2") (pinfunction "2_2") (pintype "bidirectional"))
      (node (ref "J12") (pin "3") (pinfunction "3_3") (pintype "bidirectional"))
      (node (ref "J8") (pin "3") (pinfunction "P$3_3") (pintype "bidirectional"))
      (node (ref "U4") (pin "17") (pinfunction "B3_17") (pintype "bidirectional"))
    )
    (net (code "47") (name "/IO21") (class "Default")
      (node (ref "J12") (pin "4") (pinfunction "4_4") (pintype "bidirectional"))
      (node (ref "U4") (pin "16") (pinfunction "B4_16") (pintype "bidirectional"))
    )
    (net (code "48") (name "/IO22") (class "Default")
      (node (ref "24L01-PI") (pin "2") (pinfunction "2_2") (pintype "bidirectional"))
      (node (ref "J12") (pin "5") (pinfunction "5_5") (pintype "bidirectional"))
      (node (ref "U4") (pin "15") (pinfunction "B5_15") (pintype "bidirectional"))
    )
    (net (code "49") (name "/IO23") (class "Default")
      (node (ref "J12") (pin "6") (pinfunction "6_6") (pintype "bidirectional"))
      (node (ref "PINTPI") (pin "1") (pinfunction "1_1") (pintype "bidirectional"))
      (node (ref "U4") (pin "14") (pinfunction "B6_14") (pintype "bidirectional"))
    )
    (net (code "50") (name "/IO24") (class "Default")
      (node (ref "J12") (pin "7") (pinfunction "7_7") (pintype "bidirectional"))
      (node (ref "SPI-OLED-PI") (pin "6") (pinfunction "6_6") (pintype "bidirectional"))
      (node (ref "U4") (pin "13") (pinfunction "B7_13") (pintype "bidirectional"))
    )
    (net (code "51") (name "/IO25") (class "Default")
      (node (ref "J12") (pin "8") (pinfunction "8_8") (pintype "bidirectional"))
      (node (ref "PI2C") (pin "00") (pinfunction "L_00") (pintype "bidirectional"))
      (node (ref "SPI-OLED-PI") (pin "7") (pinfunction "7_7") (pintype "bidirectional"))
      (node (ref "U4") (pin "12") (pinfunction "B8_12") (pintype "bidirectional"))
    )
    (net (code "52") (name "/IO28") (class "Default")
      (node (ref "J11") (pin "1") (pinfunction "P$1_1") (pintype "bidirectional"))
      (node (ref "PLED3") (pin "00") (pinfunction "L_00") (pintype "bidirectional"))
      (node (ref "U3") (pin "13") (pinfunction "B1_13") (pintype "bidirectional"))
    )
    (net (code "53") (name "/IO29") (class "Default")
      (node (ref "J11") (pin "2") (pinfunction "P$2_2") (pintype "bidirectional"))
      (node (ref "U3") (pin "12") (pinfunction "B2_12") (pintype "bidirectional"))
    )
    (net (code "54") (name "/IO30") (class "Default")
      (node (ref "J11") (pin "3") (pinfunction "P$3_3") (pintype "bidirectional"))
      (node (ref "U3") (pin "11") (pinfunction "B3_11") (pintype "bidirectional"))
    )
    (net (code "55") (name "/IO31") (class "Default")
      (node (ref "J11") (pin "4") (pinfunction "P$4_4") (pintype "bidirectional"))
      (node (ref "U3") (pin "10") (pinfunction "B4_10") (pintype "bidirectional"))
    )
    (net (code "56") (name "/IRQ") (class "Default")
      (node (ref "24L01") (pin "5") (pinfunction "5_5") (pintype "bidirectional"))
      (node (ref "24L01-PI") (pin "5") (pinfunction "5_5") (pintype "bidirectional"))
      (node (ref "PINT") (pin "2") (pinfunction "2_2") (pintype "bidirectional"))
      (node (ref "PINTPI") (pin "2") (pinfunction "2_2") (pintype "bidirectional"))
    )
    (net (code "57") (name "/MISO") (class "Default")
      (node (ref "24L01-PI") (pin "4") (pinfunction "4_4") (pintype "bidirectional"))
      (node (ref "J13") (pin "4") (pinfunction "4_4") (pintype "bidirectional"))
      (node (ref "PMISO") (pin "1") (pinfunction "1_1") (pintype "bidirectional"))
      (node (ref "U5") (pin "16") (pinfunction "B4_16") (pintype "bidirectional"))
    )
    (net (code "58") (name "/MISO-PI") (class "Default")
      (node (ref "PI-P1") (pin "21") (pinfunction "SPI_MISO_21") (pintype "input"))
      (node (ref "U5") (pin "5") (pinfunction "A4_5") (pintype "bidirectional"))
    )
    (net (code "59") (name "/MOSI") (class "Default")
      (node (ref "24L01-PI") (pin "6") (pinfunction "6_6") (pintype "bidirectional"))
      (node (ref "J13") (pin "3") (pinfunction "3_3") (pintype "bidirectional"))
      (node (ref "PMOSI") (pin "1") (pinfunction "1_1") (pintype "bidirectional"))
      (node (ref "SPI-OLED-PI") (pin "4") (pinfunction "4_4") (pintype "bidirectional"))
      (node (ref "U5") (pin "17") (pinfunction "B3_17") (pintype "bidirectional"))
    )
    (net (code "60") (name "/MOSI-PI") (class "Default")
      (node (ref "PI-P1") (pin "19") (pinfunction "SPI_MOSI_19") (pintype "output"))
      (node (ref "U5") (pin "4") (pinfunction "A3_4") (pintype "bidirectional"))
    )
    (net (code "61") (name "/OLED-RST") (class "Default")
      (node (ref "I2C-OLED") (pin "4") (pinfunction "4_4") (pintype "bidirectional"))
      (node (ref "PI2C") (pin "MM") (pinfunction "C_MM") (pintype "bidirectional"))
    )
    (net (code "62") (name "/OW") (class "Default")
      (node (ref "IC2") (pin "2") (pinfunction "1W_2") (pintype "open_collector"))
      (node (ref "JP2") (pin "2") (pinfunction "P$2_2") (pintype "bidirectional"))
      (node (ref "JP3") (pin "2") (pinfunction "P$2_2") (pintype "bidirectional"))
      (node (ref "JP4") (pin "2") (pinfunction "P$2_2") (pintype "bidirectional"))
      (node (ref "Q5") (pin "3") (pinfunction "D_3") (pintype "passive"))
    )
    (net (code "63") (name "/RESET") (class "Default")
      (node (ref "C1") (pin "1") (pinfunction "1_1") (pintype "passive"))
      (node (ref "IC1") (pin "1") (pinfunction "PC6(/RESET)_1") (pintype "bidirectional"))
      (node (ref "POWER") (pin "6") (pinfunction "6_6") (pintype "bidirectional"))
      (node (ref "R2") (pin "2") (pinfunction "2_2") (pintype "passive"))
      (node (ref "RESET") (pin "2") (pinfunction "2_2") (pintype "bidirectional"))
      (node (ref "U6") (pin "28") (pinfunction "RESET_28") (pintype "bidirectional"))
      (node (ref "U6") (pin "34") (pinfunction "RST_34") (pintype "bidirectional"))
    )
    (net (code "64") (name "/RXD") (class "Default")
      (node (ref "JRXD") (pin "1") (pinfunction "1_1") (pintype "bidirectional"))
      (node (ref "PI-SERIAL") (pin "1") (pinfunction "1_1") (pintype "bidirectional"))
      (node (ref "Q7") (pin "2") (pinfunction "S_2") (pintype "passive"))
      (node (ref "STINFO") (pin "11") (pinfunction "R_11") (pintype "bidirectional"))
    )
    (net (code "65") (name "/RXD-PI") (class "Default")
      (node (ref "PI-P1") (pin "10") (pinfunction "RXD_10") (pintype "input"))
      (node (ref "Q6") (pin "2") (pinfunction "S_2") (pintype "passive"))
    )
    (net (code "66") (name "/SCL") (class "Default")
      (node (ref "I2C") (pin "1") (pinfunction "1_1") (pintype "bidirectional"))
      (node (ref "I2C-OLED") (pin "5") (pinfunction "5_5") (pintype "bidirectional"))
      (node (ref "IC2") (pin "4") (pinfunction "SCL_4") (pintype "input"))
      (node (ref "PSCL") (pin "2") (pinfunction "2_2") (pintype "bidirectional"))
      (node (ref "Q2") (pin "2") (pinfunction "S_2") (pintype "passive"))
      (node (ref "R5") (pin "1") (pinfunction "1_1") (pintype "passive"))
    )
    (net (code "67") (name "/SCL-PI") (class "Default")
      (node (ref "PI-P1") (pin "5") (pinfunction "SCL0_5") (pintype "output"))
      (node (ref "Q4") (pin "2") (pinfunction "S_2") (pintype "passive"))
    )
    (net (code "68") (name "/SCLK") (class "Default")
      (node (ref "24L01-PI") (pin "3") (pinfunction "3_3") (pintype "bidirectional"))
      (node (ref "J13") (pin "5") (pinfunction "5_5") (pintype "bidirectional"))
      (node (ref "PCLK") (pin "1") (pinfunction "1_1") (pintype "bidirectional"))
      (node (ref "SPI-OLED-PI") (pin "5") (pinfunction "5_5") (pintype "bidirectional"))
      (node (ref "U5") (pin "15") (pinfunction "B5_15") (pintype "bidirectional"))
    )
    (net (code "69") (name "/SCLK-PI") (class "Default")
      (node (ref "PI-P1") (pin "23") (pinfunction "SPI_SCLK_23") (pintype "output"))
      (node (ref "U5") (pin "6") (pinfunction "A5_6") (pintype "bidirectional"))
    )
    (net (code "70") (name "/SDA") (class "Default")
      (node (ref "I2C") (pin "2") (pinfunction "2_2") (pintype "bidirectional"))
      (node (ref "I2C-OLED") (pin "6") (pinfunction "6_6") (pintype "bidirectional"))
      (node (ref "IC2") (pin "5") (pinfunction "SDA_5") (pintype "bidirectional"))
      (node (ref "PSDA") (pin "2") (pinfunction "2_2") (pintype "bidirectional"))
      (node (ref "Q1") (pin "2") (pinfunction "S_2") (pintype "passive"))
      (node (ref "R4") (pin "1") (pinfunction "1_1") (pintype "passive"))
    )
    (net (code "71") (name "/SDA-PI") (class "Default")
      (node (ref "PI-P1") (pin "3") (pinfunction "SDA0_3") (pintype "bidirectional"))
      (node (ref "Q3") (pin "2") (pinfunction "S_2") (pintype "passive"))
    )
    (net (code "72") (name "/SPI_CE0") (class "Default")
      (node (ref "PI-P1") (pin "24") (pinfunction "#SPI_CE0_24") (pintype "output"))
      (node (ref "U5") (pin "7") (pinfunction "A6_7") (pintype "bidirectional"))
    )
    (net (code "73") (name "/SPI_CE1") (class "Default")
      (node (ref "PI-P1") (pin "26") (pinfunction "#SPI_CE1_26") (pintype "output"))
      (node (ref "U5") (pin "8") (pinfunction "A7_8") (pintype "bidirectional"))
    )
    (net (code "74") (name "/TXD") (class "Default")
      (node (ref "J13") (pin "1") (pinfunction "1_1") (pintype "bidirectional"))
      (node (ref "JTXD") (pin "1") (pinfunction "1_1") (pintype "bidirectional"))
      (node (ref "PI-SERIAL") (pin "2") (pinfunction "2_2") (pintype "bidirectional"))
      (node (ref "U5") (pin "20") (pinfunction "B1_20") (pintype "bidirectional"))
    )
    (net (code "75") (name "/TXD-PI") (class "Default")
      (node (ref "PI-P1") (pin "8") (pinfunction "TXD_8") (pintype "output"))
      (node (ref "U5") (pin "1") (pinfunction "A1_1") (pintype "bidirectional"))
    )
    (net (code "76") (name "/VIN") (class "Default")
      (node (ref "C6") (pin "+") (pinfunction "+_+") (pintype "passive"))
      (node (ref "D1") (pin "-") (pinfunction "-_-") (pintype "passive"))
      (node (ref "POWER") (pin "1") (pinfunction "1_1") (pintype "bidirectional"))
      (node (ref "PPWM") (pin "11") (pinfunction "R_11") (pintype "bidirectional"))
      (node (ref "U1") (pin "1") (pinfunction "IN_1") (pintype "bidirectional"))
      (node (ref "U6") (pin "23") (pinfunction "VIN_23") (pintype "bidirectional"))
    )
    (net (code "77") (name "3V3-EXT") (class "Default")
      (node (ref "C10") (pin "2") (pinfunction "2_2") (pintype "passive"))
      (node (ref "PI_VCC_EXT") (pin "CH1B") (pinfunction "CH1B_CH1B") (pintype "bidirectional"))
      (node (ref "U2") (pin "2") (pinfunction "OUT_2") (pintype "bidirectional"))
      (node (ref "U2") (pin "TER") (pinfunction "TAB_TER") (pintype "bidirectional"))
    )
    (net (code "78") (name "3V3-PI") (class "Default")
      (node (ref "C11") (pin "1") (pinfunction "1_1") (pintype "passive"))
      (node (ref "C12") (pin "1") (pinfunction "1_1") (pintype "passive"))
      (node (ref "C13") (pin "1") (pinfunction "1_1") (pintype "passive"))
      (node (ref "PI-P1") (pin "1") (pinfunction "3.3V_1") (pintype "power_in"))
      (node (ref "PI-P1") (pin "P5.2") (pinfunction "3.3V_P5.2") (pintype "power_in"))
      (node (ref "PI_VCC_EXT") (pin "CH1A") (pinfunction "CH1A_CH1A") (pintype "bidirectional"))
      (node (ref "Q3") (pin "1") (pinfunction "G_1") (pintype "passive"))
      (node (ref "Q4") (pin "1") (pinfunction "G_1") (pintype "passive"))
      (node (ref "Q6") (pin "1") (pinfunction "G_1") (pintype "passive"))
      (node (ref "U3") (pin "1") (pinfunction "VCCA_1") (pintype "bidirectional"))
      (node (ref "U3") (pin "8") (pinfunction "OE_8") (pintype "bidirectional"))
      (node (ref "U4") (pin "10") (pinfunction "OE_10") (pintype "bidirectional"))
      (node (ref "U4") (pin "2") (pinfunction "VCCA_2") (pintype "bidirectional"))
      (node (ref "U5") (pin "10") (pinfunction "OE_10") (pintype "bidirectional"))
      (node (ref "U5") (pin "2") (pinfunction "VCCA_2") (pintype "bidirectional"))
    )
    (net (code "79") (name "5V-EXT") (class "Default")
      (node (ref "C7") (pin "+") (pinfunction "+_+") (pintype "passive"))
      (node (ref "C8") (pin "2") (pinfunction "2_2") (pintype "passive"))
      (node (ref "JVDD") (pin "1") (pinfunction "1_1") (pintype "bidirectional"))
      (node (ref "PI_VCC_EXT") (pin "CH2B") (pinfunction "CH2B_CH2B") (pintype "bidirectional"))
      (node (ref "U1") (pin "2") (pinfunction "OUT_2") (pintype "bidirectional"))
      (node (ref "U2") (pin "3") (pinfunction "IN_3") (pintype "bidirectional"))
    )
    (net (code "80") (name "5V-PI") (class "Default")
      (node (ref "PI-P1") (pin "2") (pinfunction "5.0V_2") (pintype "power_in"))
      (node (ref "PI-P1") (pin "P5.1") (pinfunction "5.0V_P5.1") (pintype "power_in"))
      (node (ref "PI_VCC_EXT") (pin "CH2A") (pinfunction "CH2A_CH2A") (pintype "bidirectional"))
      (node (ref "PLED2") (pin "11") (pinfunction "R_11") (pintype "bidirectional"))
    )
    (net (code "81") (name "GND") (class "Default")
      (node (ref "24L01") (pin "1") (pinfunction "1_1") (pintype "bidirectional"))
      (node (ref "24L01-PI") (pin "1") (pinfunction "1_1") (pintype "bidirectional"))
      (node (ref "ARDUINO-SERIAL") (pin "4") (pinfunction "4_4") (pintype "bidirectional"))
      (node (ref "C10") (pin "1") (pinfunction "1_1") (pintype "passive"))
      (node (ref "C11") (pin "2") (pinfunction "2_2") (pintype "passive"))
      (node (ref "C12") (pin "2") (pinfunction "2_2") (pintype "passive"))
      (node (ref "C13") (pin "2") (pinfunction "2_2") (pintype "passive"))
      (node (ref "C14") (pin "2") (pinfunction "2_2") (pintype "passive"))
      (node (ref "C15") (pin "2") (pinfunction "2_2") (pintype "passive"))
      (node (ref "C16") (pin "2") (pinfunction "2_2") (pintype "passive"))
      (node (ref "C2") (pin "2") (pinfunction "2_2") (pintype "passive"))
      (node (ref "C3") (pin "2") (pinfunction "2_2") (pintype "passive"))
      (node (ref "C4") (pin "1") (pinfunction "1_1") (pintype "passive"))
      (node (ref "C5") (pin "2") (pinfunction "2_2") (pintype "passive"))
      (node (ref "C6") (pin "-") (pinfunction "-_-") (pintype "passive"))
      (node (ref "C7") (pin "-") (pinfunction "-_-") (pintype "passive"))
      (node (ref "C8") (pin "1") (pinfunction "1_1") (pintype "passive"))
      (node (ref "C9") (pin "2") (pinfunction "2_2") (pintype "passive"))
      (node (ref "I2C") (pin "4") (pinfunction "4_4") (pintype "bidirectional"))
      (node (ref "I2C-OLED") (pin "3") (pinfunction "3_3") (pintype "bidirectional"))
      (node (ref "IC1") (pin "22") (pinfunction "AGND_22") (pintype "bidirectional"))
      (node (ref "IC1") (pin "8") (pinfunction "GND_8") (pintype "bidirectional"))
      (node (ref "IC2") (pin "3") (pinfunction "GND_3") (pintype "power_in"))
      (node (ref "J1") (pin "5") (pinfunction "5_5") (pintype "bidirectional"))
      (node (ref "J1") (pin "6") (pinfunction "6_6") (pintype "bidirectional"))
      (node (ref "J2") (pin "2") (pinfunction "P$2_2") (pintype "bidirectional"))
      (node (ref "J3") (pin "2") (pinfunction "P$2_2") (pintype "bidirectional"))
      (node (ref "J4") (pin "2") (pinfunction "P$2_2") (pintype "bidirectional"))
      (node (ref "J5") (pin "2") (pinfunction "P$2_2") (pintype "bidirectional"))
      (node (ref "J6") (pin "2") (pinfunction "P$2_2") (pintype "bidirectional"))
      (node (ref "J7") (pin "2") (pinfunction "P$2_2") (pintype "bidirectional"))
      (node (ref "J8") (pin "2") (pinfunction "P$2_2") (pintype "bidirectional"))
      (node (ref "J9") (pin "-") (pinfunction "-_-") (pintype "bidirectional"))
      (node (ref "J9") (pin "CDN") (pinfunction "CDN_CDN") (pintype "bidirectional"))
      (node (ref "JP2") (pin "3") (pinfunction "P$3_3") (pintype "bidirectional"))
      (node (ref "JP3") (pin "3") (pinfunction "P$3_3") (pintype "bidirectional"))
      (node (ref "JP4") (pin "3") (pinfunction "P$3_3") (pintype "bidirectional"))
      (node (ref "LED1") (pin "-") (pinfunction "-_-") (pintype "passive"))
      (node (ref "LED2") (pin "-") (pinfunction "-_-") (pintype "passive"))
      (node (ref "LED3") (pin "-") (pinfunction "-_-") (pintype "passive"))
      (node (ref "OK1") (pin "3") (pinfunction "E_3") (pintype "passive"))
      (node (ref "PB1") (pin "7") (pinfunction "7_7") (pintype "bidirectional"))
      (node (ref "PI-P1") (pin "6") (pinfunction "GND_6") (pintype "power_in"))
      (node (ref "PI-P1") (pin "P5.7") (pinfunction "GND_P5.7") (pintype "power_in"))
      (node (ref "PI-P1") (pin "P5.8") (pinfunction "GND_P5.8") (pintype "power_in"))
      (node (ref "PI-SERIAL") (pin "4") (pinfunction "4_4") (pintype "bidirectional"))
      (node (ref "POWER") (pin "2") (pinfunction "2_2") (pintype "bidirectional"))
      (node (ref "POWER") (pin "3") (pinfunction "3_3") (pintype "bidirectional"))
      (node (ref "POWER-PI") (pin "1") (pinfunction "1_1") (pintype "bidirectional"))
      (node (ref "POWER-PI") (pin "S1") (pinfunction "S1_S1") (pintype "bidirectional"))
      (node (ref "POWER-PI") (pin "S2") (pinfunction "S2_S2") (pintype "bidirectional"))
      (node (ref "R6") (pin "1") (pinfunction "1_1") (pintype "passive"))
      (node (ref "R7") (pin "1") (pinfunction "1_1") (pintype "passive"))
      (node (ref "RESET") (pin "1") (pinfunction "1_1") (pintype "bidirectional"))
      (node (ref "RESET") (pin "S1") (pinfunction "S1_S1") (pintype "bidirectional"))
      (node (ref "RESET") (pin "S2") (pinfunction "S2_S2") (pintype "bidirectional"))
      (node (ref "SPI-OLED") (pin "1") (pinfunction "1_1") (pintype "bidirectional"))
      (node (ref "SPI-OLED-PI") (pin "1") (pinfunction "1_1") (pintype "bidirectional"))
      (node (ref "U1") (pin "3") (pinfunction "GND_3") (pintype "bidirectional"))
      (node (ref "U2") (pin "1") (pinfunction "GND_1") (pintype "bidirectional"))
      (node (ref "U3") (pin "7") (pinfunction "GND_7") (pintype "bidirectional"))
      (node (ref "U4") (pin "11") (pinfunction "GND_11") (pintype "bidirectional"))
      (node (ref "U5") (pin "11") (pinfunction "GND_11") (pintype "bidirectional"))
      (node (ref "U6") (pin "15") (pinfunction "GND_15") (pintype "bidirectional"))
      (node (ref "U6") (pin "24") (pinfunction "GND_24") (pintype "bidirectional"))
      (node (ref "U6") (pin "25") (pinfunction "GND_25") (pintype "bidirectional"))
      (node (ref "U6") (pin "33") (pinfunction "GND_33") (pintype "bidirectional"))
    )
    (net (code "82") (name "Net-(D1-Pad+)") (class "Default")
      (node (ref "D1") (pin "+") (pinfunction "+_+") (pintype "passive"))
      (node (ref "J9") (pin "+") (pinfunction "+_+") (pintype "bidirectional"))
    )
    (net (code "83") (name "Net-(IC1-PB6(XTAL1{slash}TOSC1))") (class "Default")
      (node (ref "C2") (pin "1") (pinfunction "1_1") (pintype "passive"))
      (node (ref "IC1") (pin "9") (pinfunction "PB6(XTAL1/TOSC1)_9") (pintype "bidirectional"))
      (node (ref "X1") (pin "2") (pinfunction "2_2") (pintype "passive"))
    )
    (net (code "84") (name "Net-(IC1-PB7(XTAL2{slash}TOSC2))") (class "Default")
      (node (ref "C3") (pin "1") (pinfunction "1_1") (pintype "passive"))
      (node (ref "IC1") (pin "10") (pinfunction "PB7(XTAL2/TOSC2)_10") (pintype "bidirectional"))
      (node (ref "X1") (pin "1") (pinfunction "1_1") (pintype "passive"))
    )
    (net (code "85") (name "Net-(IC2A-AD0)") (class "Default")
      (node (ref "IC2") (pin "8") (pinfunction "AD0_8") (pintype "input"))
      (node (ref "PAD2") (pin "1") (pinfunction "1_1") (pintype "bidirectional"))
      (node (ref "R6") (pin "2") (pinfunction "2_2") (pintype "passive"))
    )
    (net (code "86") (name "Net-(IC2A-AD1)") (class "Default")
      (node (ref "IC2") (pin "7") (pinfunction "AD1_7") (pintype "input"))
      (node (ref "PAD1") (pin "1") (pinfunction "1_1") (pintype "bidirectional"))
      (node (ref "R7") (pin "2") (pinfunction "2_2") (pintype "passive"))
    )
    (net (code "87") (name "Net-(IC2A-PCT)") (class "Default")
      (node (ref "IC2") (pin "6") (pinfunction "PCT_6") (pintype "output"))
      (node (ref "Q5") (pin "1") (pinfunction "G_1") (pintype "passive"))
    )
    (net (code "88") (name "Net-(J1-Pad4)") (class "Default")
      (node (ref "J1") (pin "4") (pinfunction "4_4") (pintype "bidirectional"))
      (node (ref "JVDD") (pin "2") (pinfunction "2_2") (pintype "bidirectional"))
    )
    (net (code "89") (name "Net-(J2-P$1)") (class "Default")
      (node (ref "J2") (pin "1") (pinfunction "P$1_1") (pintype "bidirectional"))
      (node (ref "J3") (pin "1") (pinfunction "P$1_1") (pintype "bidirectional"))
      (node (ref "J4") (pin "1") (pinfunction "P$1_1") (pintype "bidirectional"))
      (node (ref "J5") (pin "1") (pinfunction "P$1_1") (pintype "bidirectional"))
      (node (ref "J6") (pin "1") (pinfunction "P$1_1") (pintype "bidirectional"))
      (node (ref "J7") (pin "1") (pinfunction "P$1_1") (pintype "bidirectional"))
      (node (ref "J8") (pin "1") (pinfunction "P$1_1") (pintype "bidirectional"))
      (node (ref "PPWM") (pin "MM") (pinfunction "C_MM") (pintype "bidirectional"))
    )
    (net (code "90") (name "Net-(J14-Pad2)") (class "Default")
      (node (ref "J14") (pin "2") (pinfunction "2_2") (pintype "bidirectional"))
      (node (ref "R1") (pin "2") (pinfunction "2_2") (pintype "passive"))
    )
    (net (code "91") (name "Net-(LED1-Pad+)") (class "Default")
      (node (ref "LED1") (pin "+") (pinfunction "+_+") (pintype "passive"))
      (node (ref "R9") (pin "2") (pinfunction "2_2") (pintype "passive"))
    )
    (net (code "92") (name "Net-(LED2-Pad+)") (class "Default")
      (node (ref "LED2") (pin "+") (pinfunction "+_+") (pintype "passive"))
      (node (ref "R10") (pin "2") (pinfunction "2_2") (pintype "passive"))
    )
    (net (code "93") (name "Net-(LED3-Pad+)") (class "Default")
      (node (ref "LED3") (pin "+") (pinfunction "+_+") (pintype "passive"))
      (node (ref "R11") (pin "2") (pinfunction "2_2") (pintype "passive"))
    )
    (net (code "94") (name "Net-(OK1-AC1)") (class "Default")
      (node (ref "OK1") (pin "1") (pinfunction "AC1_1") (pintype "passive"))
      (node (ref "R1") (pin "1") (pinfunction "1_1") (pintype "passive"))
    )
    (net (code "95") (name "Net-(OK1-AC2)") (class "Default")
      (node (ref "J14") (pin "1") (pinfunction "1_1") (pintype "bidirectional"))
      (node (ref "OK1") (pin "2") (pinfunction "AC2_2") (pintype "passive"))
    )
    (net (code "96") (name "Net-(OK1-C)") (class "Default")
      (node (ref "OK1") (pin "4") (pinfunction "C_4") (pintype "passive"))
      (node (ref "STINFO") (pin "MM") (pinfunction "C_MM") (pintype "bidirectional"))
    )
    (net (code "97") (name "Net-(PLED1-C)") (class "Default")
      (node (ref "PLED1") (pin "MM") (pinfunction "C_MM") (pintype "bidirectional"))
      (node (ref "R9") (pin "1") (pinfunction "1_1") (pintype "passive"))
    )
    (net (code "98") (name "Net-(PLED2-C)") (class "Default")
      (node (ref "PLED2") (pin "MM") (pinfunction "C_MM") (pintype "bidirectional"))
      (node (ref "R10") (pin "1") (pinfunction "1_1") (pintype "passive"))
    )
    (net (code "99") (name "Net-(PLED3-C)") (class "Default")
      (node (ref "PLED3") (pin "MM") (pinfunction "C_MM") (pintype "bidirectional"))
      (node (ref "R11") (pin "1") (pinfunction "1_1") (pintype "passive"))
    )
    (net (code "100") (name "Net-(POWER-PI-Pad2)") (class "Default")
      (node (ref "POWER-PI") (pin "2") (pinfunction "2_2") (pintype "bidirectional"))
      (node (ref "PWR-PI") (pin "2") (pinfunction "2_2") (pintype "bidirectional"))
      (node (ref "R3") (pin "2") (pinfunction "2_2") (pintype "passive"))
    )
    (net (code "101") (name "Net-(PSSPI-C)") (class "Default")
      (node (ref "PSSPI") (pin "MM") (pinfunction "C_MM") (pintype "bidirectional"))
      (node (ref "SPI-OLED-PI") (pin "8") (pinfunction "8_8") (pintype "bidirectional"))
    )
    (net (code "102") (name "Net-(Q1-D)") (class "Default")
      (node (ref "Q1") (pin "3") (pinfunction "D_3") (pintype "passive"))
      (node (ref "Q3") (pin "3") (pinfunction "D_3") (pintype "passive"))
    )
    (net (code "103") (name "Net-(Q2-D)") (class "Default")
      (node (ref "Q2") (pin "3") (pinfunction "D_3") (pintype "passive"))
      (node (ref "Q4") (pin "3") (pinfunction "D_3") (pintype "passive"))
    )
    (net (code "104") (name "Net-(Q6-D)") (class "Default")
      (node (ref "Q6") (pin "3") (pinfunction "D_3") (pintype "passive"))
      (node (ref "Q7") (pin "3") (pinfunction "D_3") (pintype "passive"))
    )
    (net (code "105") (name "VDD") (class "Default")
      (node (ref "3V3_VDD_5V") (pin "COM1") (pinfunction "COM1_COM1") (pintype "bidirectional"))
      (node (ref "3V3_VDD_5V") (pin "COM2") (pinfunction "COM2_COM2") (pintype "bidirectional"))
      (node (ref "ARDUINO-SERIAL") (pin "3") (pinfunction "3_3") (pintype "bidirectional"))
      (node (ref "C14") (pin "1") (pinfunction "1_1") (pintype "passive"))
      (node (ref "C15") (pin "1") (pinfunction "1_1") (pintype "passive"))
      (node (ref "C16") (pin "1") (pinfunction "1_1") (pintype "passive"))
      (node (ref "C4") (pin "2") (pinfunction "2_2") (pintype "passive"))
      (node (ref "C9") (pin "1") (pinfunction "1_1") (pintype "passive"))
      (node (ref "I2C") (pin "3") (pinfunction "3_3") (pintype "bidirectional"))
      (node (ref "I2C-OLED") (pin "1") (pinfunction "1_1") (pintype "bidirectional"))
      (node (ref "IC1") (pin "20") (pinfunction "AVCC_20") (pintype "bidirectional"))
      (node (ref "IC1") (pin "7") (pinfunction "VCC_7") (pintype "bidirectional"))
      (node (ref "IC2") (pin "1") (pinfunction "VDD_1") (pintype "power_in"))
      (node (ref "JP2") (pin "1") (pinfunction "P$1_1") (pintype "bidirectional"))
      (node (ref "JP3") (pin "1") (pinfunction "P$1_1") (pintype "bidirectional"))
      (node (ref "JP4") (pin "1") (pinfunction "P$1_1") (pintype "bidirectional"))
      (node (ref "PAD1") (pin "2") (pinfunction "2_2") (pintype "bidirectional"))
      (node (ref "PAD2") (pin "2") (pinfunction "2_2") (pintype "bidirectional"))
      (node (ref "PI-SERIAL") (pin "3") (pinfunction "3_3") (pintype "bidirectional"))
      (node (ref "PLED2") (pin "00") (pinfunction "L_00") (pintype "bidirectional"))
      (node (ref "POWER") (pin "4") (pinfunction "4_4") (pintype "bidirectional"))
      (node (ref "PPWM") (pin "00") (pinfunction "L_00") (pintype "bidirectional"))
      (node (ref "Q1") (pin "1") (pinfunction "G_1") (pintype "passive"))
      (node (ref "Q2") (pin "1") (pinfunction "G_1") (pintype "passive"))
      (node (ref "Q5") (pin "2") (pinfunction "S_2") (pintype "passive"))
      (node (ref "Q7") (pin "1") (pinfunction "G_1") (pintype "passive"))
      (node (ref "R2") (pin "1") (pinfunction "1_1") (pintype "passive"))
      (node (ref "R3") (pin "1") (pinfunction "1_1") (pintype "passive"))
      (node (ref "R4") (pin "2") (pinfunction "2_2") (pintype "passive"))
      (node (ref "R5") (pin "2") (pinfunction "2_2") (pintype "passive"))
      (node (ref "SPI-OLED") (pin "3") (pinfunction "3_3") (pintype "bidirectional"))
      (node (ref "SPI-OLED-PI") (pin "3") (pinfunction "3_3") (pintype "bidirectional"))
      (node (ref "U3") (pin "14") (pinfunction "VCCB_14") (pintype "bidirectional"))
      (node (ref "U4") (pin "19") (pinfunction "VCCB_19") (pintype "bidirectional"))
      (node (ref "U5") (pin "19") (pinfunction "VCCB_19") (pintype "bidirectional"))
      (node (ref "U6") (pin "26") (pinfunction "5V_26") (pintype "bidirectional"))
      (node (ref "U6") (pin "31") (pinfunction "VCC_31") (pintype "bidirectional"))
    )
    (net (code "106") (name "unconnected-(I2C-OLED-Pad2)") (class "Default")
      (node (ref "I2C-OLED") (pin "2") (pinfunction "2_2") (pintype "bidirectional"))
    )
    (net (code "107") (name "unconnected-(IC1-AREF-Pad21)") (class "Default")
      (node (ref "IC1") (pin "21") (pinfunction "AREF_21") (pintype "bidirectional"))
    )
    (net (code "108") (name "unconnected-(PI-P1-DNC-Pad4)") (class "Default")
      (node (ref "PI-P1") (pin "4") (pinfunction "DNC_4") (pintype "no_connect"))
    )
    (net (code "109") (name "unconnected-(PI-P1-DNC-Pad9)") (class "Default")
      (node (ref "PI-P1") (pin "9") (pinfunction "DNC_9") (pintype "no_connect"))
    )
    (net (code "110") (name "unconnected-(PI-P1-DNC-Pad14)") (class "Default")
      (node (ref "PI-P1") (pin "14") (pinfunction "DNC_14") (pintype "no_connect"))
    )
    (net (code "111") (name "unconnected-(PI-P1-DNC-Pad17)") (class "Default")
      (node (ref "PI-P1") (pin "17") (pinfunction "DNC_17") (pintype "no_connect"))
    )
    (net (code "112") (name "unconnected-(PI-P1-DNC-Pad20)") (class "Default")
      (node (ref "PI-P1") (pin "20") (pinfunction "DNC_20") (pintype "no_connect"))
    )
    (net (code "113") (name "unconnected-(PI-P1-DNC-Pad25)") (class "Default")
      (node (ref "PI-P1") (pin "25") (pinfunction "DNC_25") (pintype "no_connect"))
    )
    (net (code "114") (name "unconnected-(SPI-OLED-PI-Pad2)") (class "Default")
      (node (ref "SPI-OLED-PI") (pin "2") (pinfunction "2_2") (pintype "bidirectional"))
    )
    (net (code "115") (name "unconnected-(SPI-OLED-Pad2)") (class "Default")
      (node (ref "SPI-OLED") (pin "2") (pinfunction "2_2") (pintype "bidirectional"))
    )
  )
)
